# OpenLog.net
KiCad netlist of a schematic drawn in EAGLE
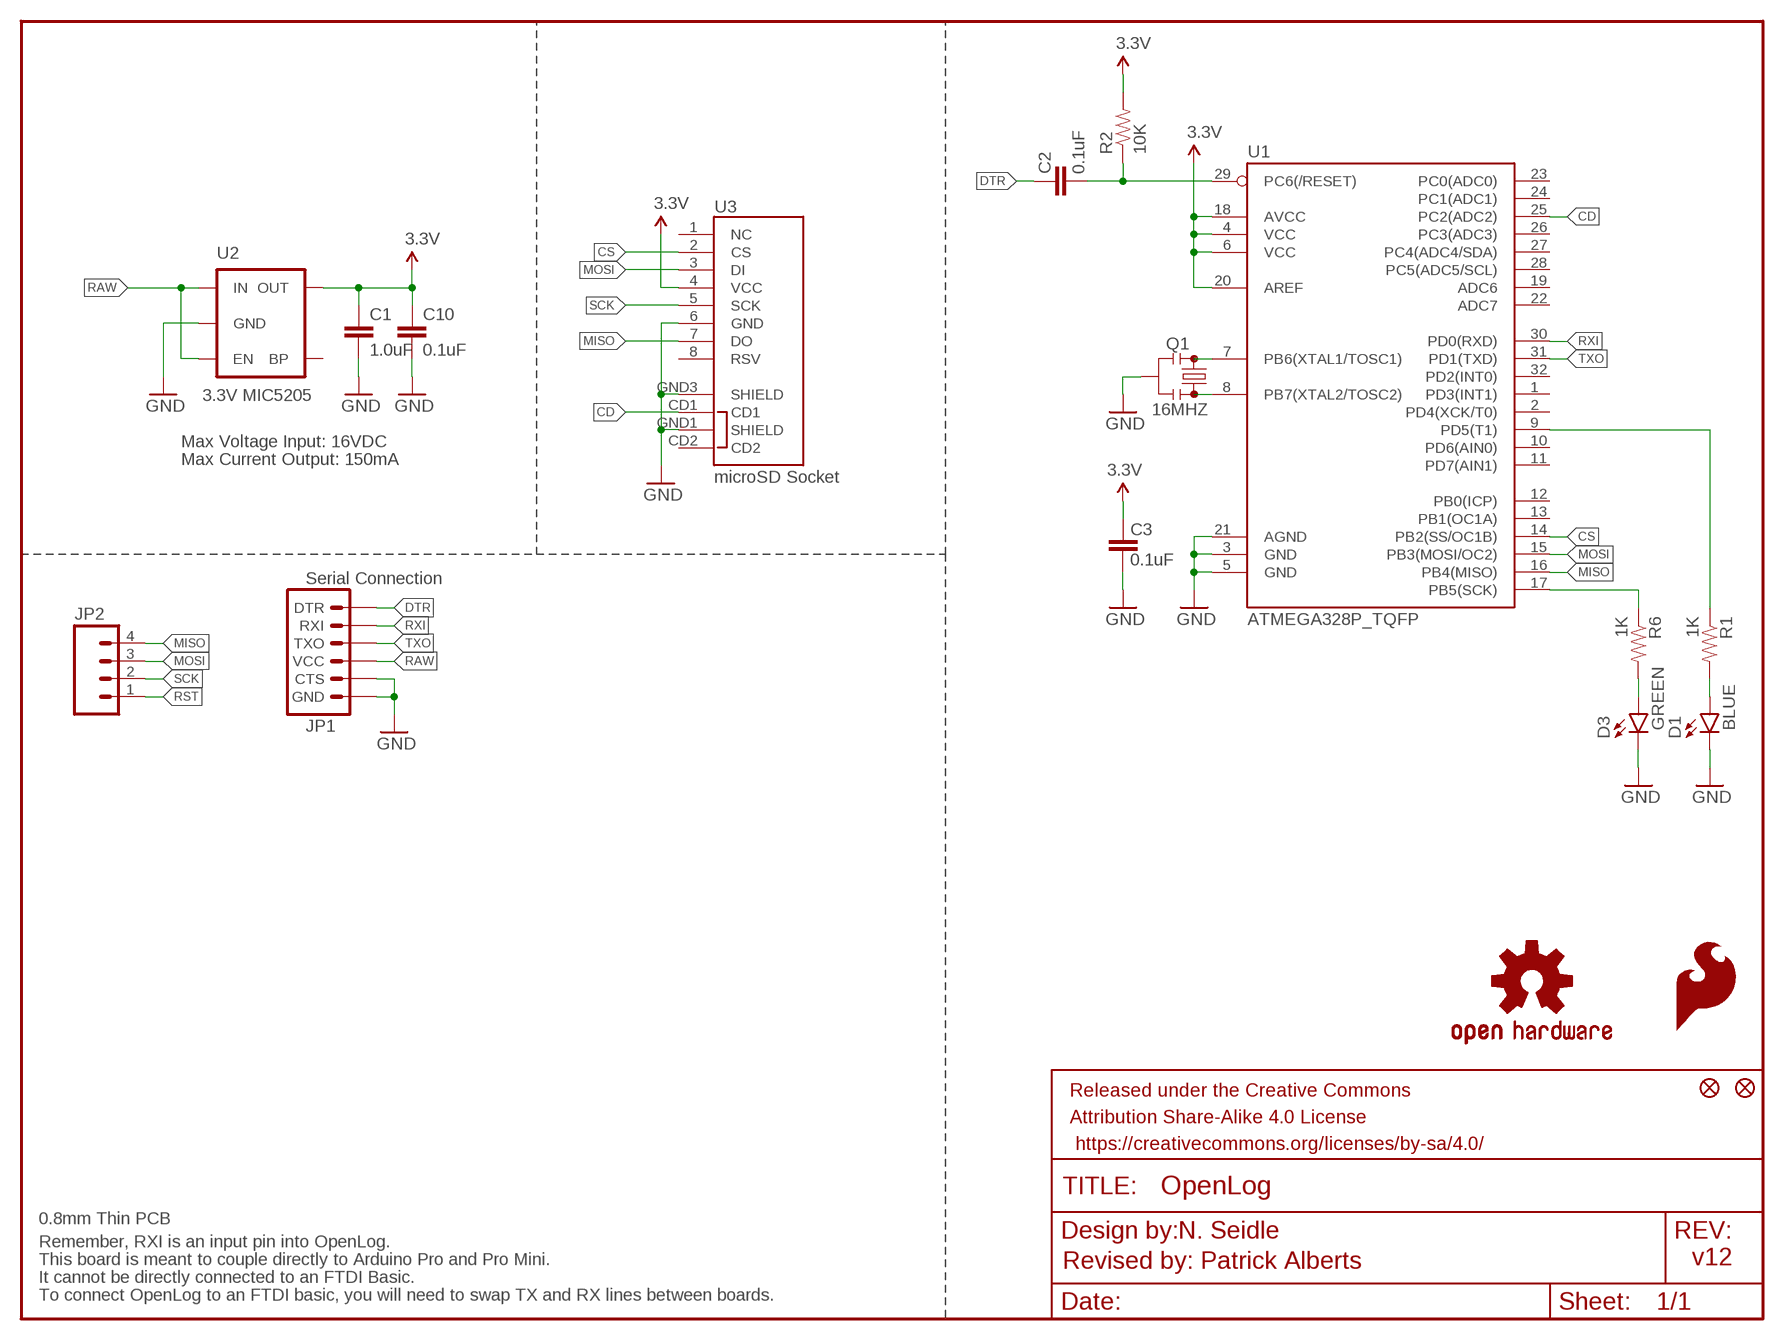
[diagram p0: schematic, sheet 1]

(export (version "E")
  (design (tool "Eeschema 10.0.6"))
  (components
    (comp (ref "C1")
      (value "1.0uF")
      (footprint "eagle-import:0603-CAP")
      (libsource (lib "eagle-import") (part "1.0UF-16V-10%(0603)"))
    )
    (comp (ref "C2")
      (value "0.1uF")
      (footprint "eagle-import:0603-CAP")
      (libsource (lib "eagle-import") (part "0.1UF-25V(+80/-20%)(0603)"))
    )
    (comp (ref "C3")
      (value "0.1uF")
      (footprint "eagle-import:0603-CAP")
      (libsource (lib "eagle-import") (part "0.1UF-25V(+80/-20%)(0603)"))
    )
    (comp (ref "C10")
      (value "0.1uF")
      (footprint "eagle-import:0603-CAP")
      (libsource (lib "eagle-import") (part "0.1UF-25V(+80/-20%)(0603)"))
    )
    (comp (ref "D1")
      (value "BLUE")
      (footprint "eagle-import:LED-0603")
      (libsource (lib "eagle-import") (part "LED-BLUE0603"))
    )
    (comp (ref "D3")
      (value "GREEN")
      (footprint "eagle-import:LED-0603")
      (libsource (lib "eagle-import") (part "LED-GREEN0603"))
    )
    (comp (ref "FID1")
      (value "FIDUCIALUFIDUCIAL")
      (footprint "eagle-import:MICRO-FIDUCIAL")
      (libsource (lib "eagle-import") (part "FIDUCIALUFIDUCIAL"))
    )
    (comp (ref "FID2")
      (value "FIDUCIALUFIDUCIAL")
      (footprint "eagle-import:MICRO-FIDUCIAL")
      (libsource (lib "eagle-import") (part "FIDUCIALUFIDUCIAL"))
    )
    (comp (ref "FRAME1")
      (value "FRAME-LETTER")
      (footprint "eagle-import:CREATIVE_COMMONS")
      (fields (field (name "DESIGNER") "NAME"))
      (libsource (lib "eagle-import") (part "FRAME-LETTER"))
    )
    (comp (ref "JP1")
      (value "Serial Connection")
      (footprint "eagle-import:1X06")
      (libsource (lib "eagle-import") (part "ARDUINO_SERIAL_PROGRAMPTH"))
    )
    (comp (ref "JP2")
      (value "M04PTH")
      (footprint "eagle-import:1X04")
      (libsource (lib "eagle-import") (part "M04PTH"))
    )
    (comp (ref "LOGO1")
      (value "SFE_LOGO_FLAME.1_INCH")
      (footprint "eagle-import:SFE_LOGO_FLAME_.1")
      (libsource (lib "eagle-import") (part "SFE_LOGO_FLAME.1_INCH"))
    )
    (comp (ref "LOGO2")
      (value "OSHW-LOGOS")
      (footprint "eagle-import:OSHW-LOGO-S")
      (libsource (lib "eagle-import") (part "OSHW-LOGOS"))
    )
    (comp (ref "Q1")
      (value "16MHZ")
      (footprint "eagle-import:RESONATOR-SMD")
      (libsource (lib "eagle-import") (part "RESONATOR16MHZ"))
    )
    (comp (ref "R1")
      (value "1K")
      (footprint "eagle-import:0603-RES")
      (libsource (lib "eagle-import") (part "1KOHM-1/10W-1%(0603)"))
    )
    (comp (ref "R2")
      (value "10K")
      (footprint "eagle-import:0603-RES")
      (libsource (lib "eagle-import") (part "10KOHM-1/10W-1%(0603)0603"))
    )
    (comp (ref "R6")
      (value "1K")
      (footprint "eagle-import:0603-RES")
      (libsource (lib "eagle-import") (part "1KOHM-1/10W-1%(0603)"))
    )
    (comp (ref "U1")
      (value "ATMEGA328P_TQFP")
      (footprint "eagle-import:TQFP32-08")
      (libsource (lib "eagle-import") (part "ATMEGA328P_TQFP"))
    )
    (comp (ref "U2")
      (value "3.3V MIC5205")
      (footprint "eagle-import:SOT23-5")
      (libsource (lib "eagle-import") (part "MIC52053.3V"))
    )
    (comp (ref "U3")
      (value "microSD Socket")
      (footprint "eagle-import:MICROSD_1_1")
      (libsource (lib "eagle-import") (part "USD-SOCKET"))
    )
  )
  (nets
    (net (code "1") (name "3.3V") (class "Default")
      (node (ref "C1") (pin "1") (pinfunction "1_1") (pintype "passive"))
      (node (ref "C10") (pin "1") (pinfunction "1_1") (pintype "passive"))
      (node (ref "C3") (pin "2") (pinfunction "2_2") (pintype "passive"))
      (node (ref "R2") (pin "2") (pinfunction "2_2") (pintype "passive"))
      (node (ref "U1") (pin "18") (pinfunction "AVCC_18") (pintype "bidirectional"))
      (node (ref "U1") (pin "20") (pinfunction "AREF_20") (pintype "bidirectional"))
      (node (ref "U1") (pin "4") (pinfunction "VCC_4") (pintype "bidirectional"))
      (node (ref "U1") (pin "6") (pinfunction "VCC_6") (pintype "bidirectional"))
      (node (ref "U2") (pin "5") (pinfunction "OUT_5") (pintype "passive"))
      (node (ref "U3") (pin "4") (pinfunction "VCC_4") (pintype "bidirectional"))
    )
    (net (code "2") (name "CD") (class "Default")
      (node (ref "U1") (pin "25") (pinfunction "PC2(ADC2)_25") (pintype "bidirectional"))
      (node (ref "U3") (pin "CD1") (pinfunction "CD1_CD1") (pintype "bidirectional"))
    )
    (net (code "3") (name "CS") (class "Default")
      (node (ref "U1") (pin "14") (pinfunction "PB2(SS/OC1B)_14") (pintype "bidirectional"))
      (node (ref "U3") (pin "2") (pinfunction "CS_2") (pintype "bidirectional"))
    )
    (net (code "4") (name "DTR") (class "Default")
      (node (ref "C2") (pin "2") (pinfunction "2_2") (pintype "passive"))
      (node (ref "JP1") (pin "1") (pinfunction "DTR_1") (pintype "passive"))
    )
    (net (code "5") (name "GND") (class "Default")
      (node (ref "C1") (pin "2") (pinfunction "2_2") (pintype "passive"))
      (node (ref "C10") (pin "2") (pinfunction "2_2") (pintype "passive"))
      (node (ref "C3") (pin "1") (pinfunction "1_1") (pintype "passive"))
      (node (ref "D1") (pin "C") (pinfunction "C_C") (pintype "passive"))
      (node (ref "D3") (pin "C") (pinfunction "C_C") (pintype "passive"))
      (node (ref "JP1") (pin "5") (pinfunction "CTS_5") (pintype "passive"))
      (node (ref "JP1") (pin "6") (pinfunction "GND_6") (pintype "passive"))
      (node (ref "Q1") (pin "2") (pinfunction "2_2") (pintype "passive"))
      (node (ref "U1") (pin "21") (pinfunction "AGND_21") (pintype "bidirectional"))
      (node (ref "U1") (pin "3") (pinfunction "GND_3") (pintype "bidirectional"))
      (node (ref "U1") (pin "5") (pinfunction "GND_5") (pintype "bidirectional"))
      (node (ref "U2") (pin "2") (pinfunction "GND_2") (pintype "input"))
      (node (ref "U3") (pin "6") (pinfunction "GND_6") (pintype "bidirectional"))
      (node (ref "U3") (pin "GND1") (pinfunction "SHIELD_GND1") (pintype "bidirectional"))
      (node (ref "U3") (pin "GND3") (pinfunction "SHIELD_GND3") (pintype "bidirectional"))
    )
    (net (code "6") (name "MISO") (class "Default")
      (node (ref "JP2") (pin "4") (pinfunction "4_4") (pintype "passive"))
      (node (ref "U1") (pin "16") (pinfunction "PB4(MISO)_16") (pintype "bidirectional"))
      (node (ref "U3") (pin "7") (pinfunction "DO_7") (pintype "bidirectional"))
    )
    (net (code "7") (name "MOSI") (class "Default")
      (node (ref "JP2") (pin "3") (pinfunction "3_3") (pintype "passive"))
      (node (ref "U1") (pin "15") (pinfunction "PB3(MOSI/OC2)_15") (pintype "bidirectional"))
      (node (ref "U3") (pin "3") (pinfunction "DI_3") (pintype "bidirectional"))
    )
    (net (code "8") (name "Net-(D1-PadA)") (class "Default")
      (node (ref "D1") (pin "A") (pinfunction "A_A") (pintype "passive"))
      (node (ref "R1") (pin "2") (pinfunction "2_2") (pintype "passive"))
    )
    (net (code "9") (name "Net-(D3-PadA)") (class "Default")
      (node (ref "D3") (pin "A") (pinfunction "A_A") (pintype "passive"))
      (node (ref "R6") (pin "2") (pinfunction "2_2") (pintype "passive"))
    )
    (net (code "10") (name "Net-(U1-PB6(XTAL1{slash}TOSC1))") (class "Default")
      (node (ref "Q1") (pin "3") (pinfunction "3_3") (pintype "passive"))
      (node (ref "U1") (pin "7") (pinfunction "PB6(XTAL1/TOSC1)_7") (pintype "bidirectional"))
    )
    (net (code "11") (name "Net-(U1-PB7(XTAL2{slash}TOSC2))") (class "Default")
      (node (ref "Q1") (pin "1") (pinfunction "1_1") (pintype "passive"))
      (node (ref "U1") (pin "8") (pinfunction "PB7(XTAL2/TOSC2)_8") (pintype "bidirectional"))
    )
    (net (code "12") (name "Net-(U1-PD5(T1))") (class "Default")
      (node (ref "R1") (pin "1") (pinfunction "1_1") (pintype "passive"))
      (node (ref "U1") (pin "9") (pinfunction "PD5(T1)_9") (pintype "bidirectional"))
    )
    (net (code "13") (name "RAW") (class "Default")
      (node (ref "JP1") (pin "4") (pinfunction "VCC_4") (pintype "passive"))
      (node (ref "U2") (pin "1") (pinfunction "IN_1") (pintype "input"))
      (node (ref "U2") (pin "3") (pinfunction "EN_3") (pintype "input"))
    )
    (net (code "14") (name "RST") (class "Default")
      (node (ref "C2") (pin "1") (pinfunction "1_1") (pintype "passive"))
      (node (ref "JP2") (pin "1") (pinfunction "1_1") (pintype "passive"))
      (node (ref "R2") (pin "1") (pinfunction "1_1") (pintype "passive"))
      (node (ref "U1") (pin "29") (pinfunction "PC6(/RESET)_29") (pintype "bidirectional"))
    )
    (net (code "15") (name "RXI") (class "Default")
      (node (ref "JP1") (pin "2") (pinfunction "RXI_2") (pintype "passive"))
      (node (ref "U1") (pin "30") (pinfunction "PD0(RXD)_30") (pintype "bidirectional"))
    )
    (net (code "16") (name "SCK") (class "Default")
      (node (ref "JP2") (pin "2") (pinfunction "2_2") (pintype "passive"))
      (node (ref "R6") (pin "1") (pinfunction "1_1") (pintype "passive"))
      (node (ref "U1") (pin "17") (pinfunction "PB5(SCK)_17") (pintype "bidirectional"))
      (node (ref "U3") (pin "5") (pinfunction "SCK_5") (pintype "bidirectional"))
    )
    (net (code "17") (name "TXO") (class "Default")
      (node (ref "JP1") (pin "3") (pinfunction "TXO_3") (pintype "passive"))
      (node (ref "U1") (pin "31") (pinfunction "PD1(TXD)_31") (pintype "bidirectional"))
    )
    (net (code "18") (name "unconnected-(U1-ADC6-Pad19)") (class "Default")
      (node (ref "U1") (pin "19") (pinfunction "ADC6_19") (pintype "bidirectional"))
    )
    (net (code "19") (name "unconnected-(U1-ADC7-Pad22)") (class "Default")
      (node (ref "U1") (pin "22") (pinfunction "ADC7_22") (pintype "bidirectional"))
    )
    (net (code "20") (name "unconnected-(U1-PB0(ICP)-Pad12)") (class "Default")
      (node (ref "U1") (pin "12") (pinfunction "PB0(ICP)_12") (pintype "bidirectional"))
    )
    (net (code "21") (name "unconnected-(U1-PB1(OC1A)-Pad13)") (class "Default")
      (node (ref "U1") (pin "13") (pinfunction "PB1(OC1A)_13") (pintype "bidirectional"))
    )
    (net (code "22") (name "unconnected-(U1-PC0(ADC0)-Pad23)") (class "Default")
      (node (ref "U1") (pin "23") (pinfunction "PC0(ADC0)_23") (pintype "bidirectional"))
    )
    (net (code "23") (name "unconnected-(U1-PC1(ADC1)-Pad24)") (class "Default")
      (node (ref "U1") (pin "24") (pinfunction "PC1(ADC1)_24") (pintype "bidirectional"))
    )
    (net (code "24") (name "unconnected-(U1-PC3(ADC3)-Pad26)") (class "Default")
      (node (ref "U1") (pin "26") (pinfunction "PC3(ADC3)_26") (pintype "bidirectional"))
    )
    (net (code "25") (name "unconnected-(U1-PC4(ADC4{slash}SDA)-Pad27)") (class "Default")
      (node (ref "U1") (pin "27") (pinfunction "PC4(ADC4/SDA)_27") (pintype "bidirectional"))
    )
    (net (code "26") (name "unconnected-(U1-PC5(ADC5{slash}SCL)-Pad28)") (class "Default")
      (node (ref "U1") (pin "28") (pinfunction "PC5(ADC5/SCL)_28") (pintype "bidirectional"))
    )
    (net (code "27") (name "unconnected-(U1-PD2(INT0)-Pad32)") (class "Default")
      (node (ref "U1") (pin "32") (pinfunction "PD2(INT0)_32") (pintype "bidirectional"))
    )
    (net (code "28") (name "unconnected-(U1-PD3(INT1)-Pad1)") (class "Default")
      (node (ref "U1") (pin "1") (pinfunction "PD3(INT1)_1") (pintype "bidirectional"))
    )
    (net (code "29") (name "unconnected-(U1-PD4(XCK{slash}T0)-Pad2)") (class "Default")
      (node (ref "U1") (pin "2") (pinfunction "PD4(XCK/T0)_2") (pintype "bidirectional"))
    )
    (net (code "30") (name "unconnected-(U1-PD6(AIN0)-Pad10)") (class "Default")
      (node (ref "U1") (pin "10") (pinfunction "PD6(AIN0)_10") (pintype "bidirectional"))
    )
    (net (code "31") (name "unconnected-(U1-PD7(AIN1)-Pad11)") (class "Default")
      (node (ref "U1") (pin "11") (pinfunction "PD7(AIN1)_11") (pintype "bidirectional"))
    )
    (net (code "32") (name "unconnected-(U2-BP-Pad4)") (class "Default")
      (node (ref "U2") (pin "4") (pinfunction "BP_4") (pintype "input"))
    )
    (net (code "33") (name "unconnected-(U3-NC-Pad1)") (class "Default")
      (node (ref "U3") (pin "1") (pinfunction "NC_1") (pintype "bidirectional"))
    )
    (net (code "34") (name "unconnected-(U3-PadCD2)") (class "Default")
      (node (ref "U3") (pin "CD2") (pinfunction "CD2_CD2") (pintype "bidirectional"))
    )
    (net (code "35") (name "unconnected-(U3-RSV-Pad8)") (class "Default")
      (node (ref "U3") (pin "8") (pinfunction "RSV_8") (pintype "bidirectional"))
    )
  )
)
